# InterfacesA_TRANSCEIVER.net
KiCad netlist of a schematic drawn in Altium Designer
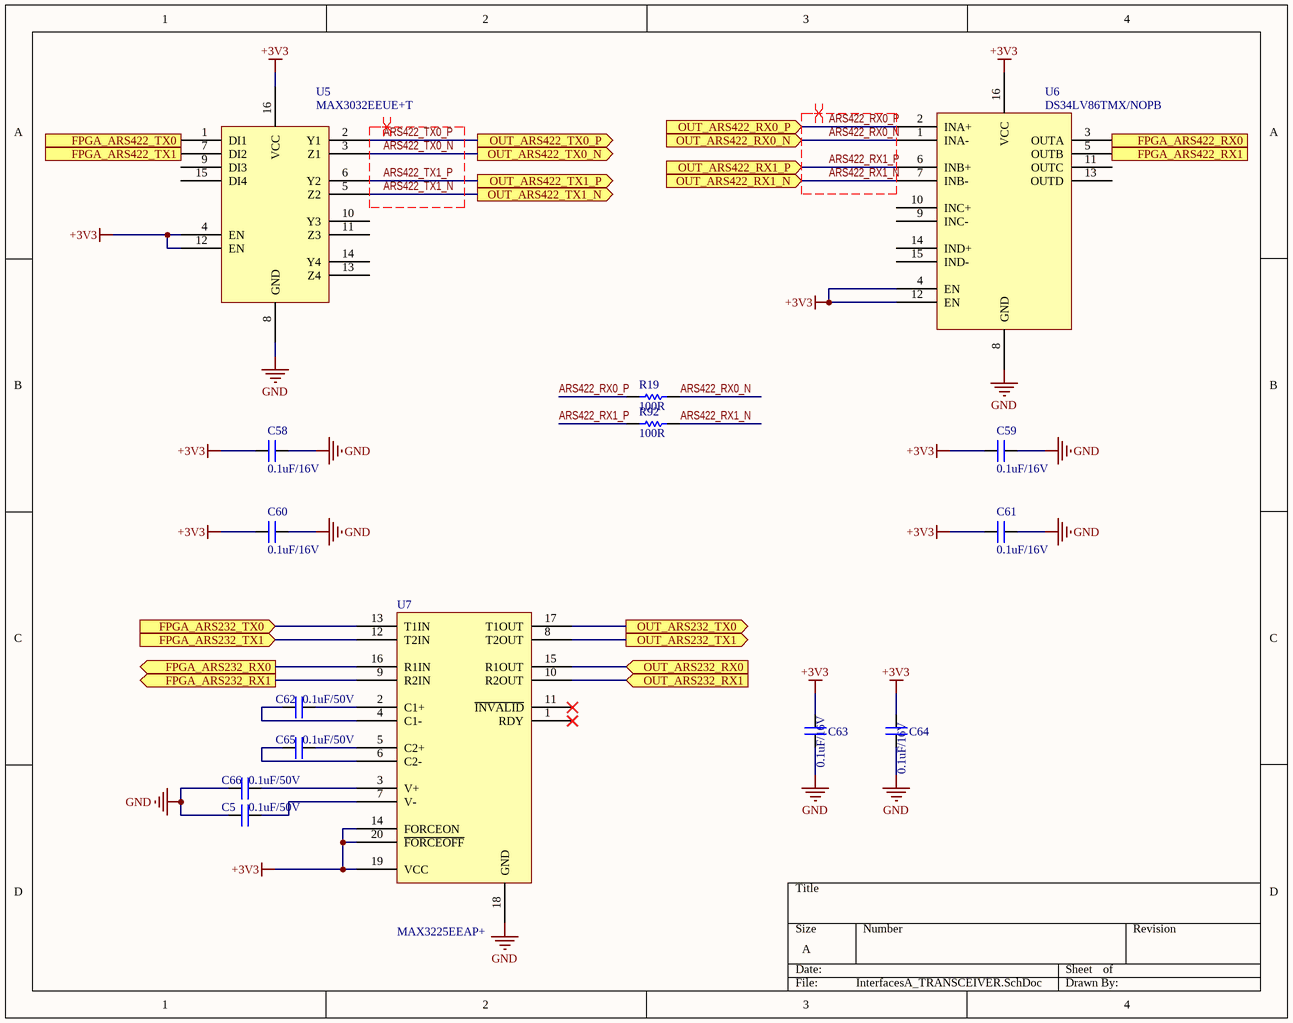
[diagram p0: InterfacesA_TRANSCEIVER.SchDoc]

(export (version "E")
  (design (tool "Eeschema 10.0.6"))
  (components
    (comp (ref "C5")
      (value "0.1uF/50V")
      (footprint "CAP_0805")
      (fields (field (name "Comment") "CAP_0805"))
      (libsource (lib "LibSGQB") (part "CAP_0603"))
    )
    (comp (ref "C58")
      (value "0.1uF/16V")
      (footprint "CAP_0805")
      (fields (field (name "Comment") "CAP_0805"))
      (libsource (lib "LibSGQB") (part "CAP_0603"))
    )
    (comp (ref "C59")
      (value "0.1uF/16V")
      (footprint "CAP_0805")
      (fields (field (name "Comment") "CAP_0805"))
      (libsource (lib "LibSGQB") (part "CAP_0603"))
    )
    (comp (ref "C60")
      (value "0.1uF/16V")
      (footprint "CAP_0805")
      (fields (field (name "Comment") "CAP_0805"))
      (libsource (lib "LibSGQB") (part "CAP_0603"))
    )
    (comp (ref "C61")
      (value "0.1uF/16V")
      (footprint "CAP_0805")
      (fields (field (name "Comment") "CAP_0805"))
      (libsource (lib "LibSGQB") (part "CAP_0603"))
    )
    (comp (ref "C62")
      (value "0.1uF/50V")
      (footprint "CAP_0805")
      (fields (field (name "Comment") "CAP_0805"))
      (libsource (lib "LibSGQB") (part "CAP_0603"))
    )
    (comp (ref "C63")
      (value "0.1uF/16V")
      (footprint "CAP_0805")
      (fields (field (name "Comment") "CAP_0805"))
      (libsource (lib "LibSGQB") (part "CAP_0603"))
    )
    (comp (ref "C64")
      (value "0.1uF/16V")
      (footprint "CAP_0805")
      (fields (field (name "Comment") "CAP_0805"))
      (libsource (lib "LibSGQB") (part "CAP_0603"))
    )
    (comp (ref "C65")
      (value "0.1uF/50V")
      (footprint "CAP_0805")
      (fields (field (name "Comment") "CAP_0805"))
      (libsource (lib "LibSGQB") (part "CAP_0603"))
    )
    (comp (ref "C66")
      (value "0.1uF/50V")
      (footprint "CAP_0805")
      (fields (field (name "Comment") "CAP_0805"))
      (libsource (lib "LibSGQB") (part "CAP_0603"))
    )
    (comp (ref "R19")
      (value "100R")
      (footprint "RES_0805")
      (fields (field (name "Comment") "RES_0805"))
      (libsource (lib "AdapterLib") (part "RES_0805"))
    )
    (comp (ref "R92")
      (value "100R")
      (footprint "RES_0805")
      (fields (field (name "Comment") "RES_0805"))
      (libsource (lib "AdapterLib") (part "RES_0805"))
    )
    (comp (ref "U5")
      (value "MAX3032EEUE+T")
      (footprint "MAX3032EEUE+T")
      (libsource (lib "AdapterLib") (part "MAX3032EEUE+T"))
    )
    (comp (ref "U6")
      (value "DS34LV86TMX/NOPB")
      (footprint "DS34LV86TMX/NOPB")
      (libsource (lib "AdapterLib") (part "DS34LV86TMX/NOPB"))
    )
    (comp (ref "U7")
      (value "MAX3225EEAP+")
      (footprint "MAX3225EEAP+")
      (libsource (lib "AdapterLib") (part "MAX3225EEAP+"))
    )
  )
  (nets
    (net (code "1") (name "+3V3") (class "Default")
      (node (ref "C58") (pin "2") (pinfunction "2_2") (pintype "passive"))
      (node (ref "C59") (pin "2") (pinfunction "2_2") (pintype "passive"))
      (node (ref "C60") (pin "2") (pinfunction "2_2") (pintype "passive"))
      (node (ref "C61") (pin "2") (pinfunction "2_2") (pintype "passive"))
      (node (ref "C63") (pin "2") (pinfunction "2_2") (pintype "passive"))
      (node (ref "C64") (pin "2") (pinfunction "2_2") (pintype "passive"))
      (node (ref "U5") (pin "12") (pinfunction "EN_12") (pintype "passive"))
      (node (ref "U5") (pin "16") (pinfunction "VCC_16") (pintype "passive"))
      (node (ref "U5") (pin "4") (pinfunction "EN_4") (pintype "passive"))
      (node (ref "U6") (pin "12") (pinfunction "EN_12") (pintype "passive"))
      (node (ref "U6") (pin "16") (pinfunction "VCC_16") (pintype "passive"))
      (node (ref "U6") (pin "4") (pinfunction "EN_4") (pintype "passive"))
      (node (ref "U7") (pin "14") (pinfunction "FORCEON_14") (pintype "passive"))
      (node (ref "U7") (pin "19") (pinfunction "VCC_19") (pintype "passive"))
      (node (ref "U7") (pin "20") (pinfunction "~{FORCEOFF}_20") (pintype "passive"))
    )
    (net (code "2") (name "/ARS422_RX0_N") (class "Default")
      (node (ref "R19") (pin "1") (pinfunction "1_1") (pintype "passive"))
      (node (ref "U6") (pin "1") (pinfunction "INA-_1") (pintype "passive"))
    )
    (net (code "3") (name "/ARS422_RX0_P") (class "Default")
      (node (ref "R19") (pin "2") (pinfunction "2_2") (pintype "passive"))
      (node (ref "U6") (pin "2") (pinfunction "INA+_2") (pintype "passive"))
    )
    (net (code "4") (name "/ARS422_RX1_N") (class "Default")
      (node (ref "R92") (pin "1") (pinfunction "1_1") (pintype "passive"))
      (node (ref "U6") (pin "7") (pinfunction "INB-_7") (pintype "passive"))
    )
    (net (code "5") (name "/ARS422_RX1_P") (class "Default")
      (node (ref "R92") (pin "2") (pinfunction "2_2") (pintype "passive"))
      (node (ref "U6") (pin "6") (pinfunction "INB+_6") (pintype "passive"))
    )
    (net (code "6") (name "/ARS422_TX0_N") (class "Default")
      (node (ref "U5") (pin "3") (pinfunction "Z1_3") (pintype "passive"))
    )
    (net (code "7") (name "/ARS422_TX0_P") (class "Default")
      (node (ref "U5") (pin "2") (pinfunction "Y1_2") (pintype "passive"))
    )
    (net (code "8") (name "/ARS422_TX1_N") (class "Default")
      (node (ref "U5") (pin "5") (pinfunction "Z2_5") (pintype "passive"))
    )
    (net (code "9") (name "/ARS422_TX1_P") (class "Default")
      (node (ref "U5") (pin "6") (pinfunction "Y2_6") (pintype "passive"))
    )
    (net (code "10") (name "/FPGA_ARS232_RX0") (class "Default")
      (node (ref "U7") (pin "16") (pinfunction "R1IN_16") (pintype "passive"))
    )
    (net (code "11") (name "/FPGA_ARS232_RX1") (class "Default")
      (node (ref "U7") (pin "9") (pinfunction "R2IN_9") (pintype "passive"))
    )
    (net (code "12") (name "/FPGA_ARS232_TX0") (class "Default")
      (node (ref "U7") (pin "13") (pinfunction "T1IN_13") (pintype "passive"))
    )
    (net (code "13") (name "/FPGA_ARS232_TX1") (class "Default")
      (node (ref "U7") (pin "12") (pinfunction "T2IN_12") (pintype "passive"))
    )
    (net (code "14") (name "/FPGA_ARS422_RX0") (class "Default")
      (node (ref "U6") (pin "3") (pinfunction "OUTA_3") (pintype "passive"))
    )
    (net (code "15") (name "/FPGA_ARS422_RX1") (class "Default")
      (node (ref "U6") (pin "5") (pinfunction "OUTB_5") (pintype "passive"))
    )
    (net (code "16") (name "/FPGA_ARS422_TX0") (class "Default")
      (node (ref "U5") (pin "1") (pinfunction "DI1_1") (pintype "passive"))
    )
    (net (code "17") (name "/FPGA_ARS422_TX1") (class "Default")
      (node (ref "U5") (pin "7") (pinfunction "DI2_7") (pintype "passive"))
    )
    (net (code "18") (name "/OUT_ARS232_RX0") (class "Default")
      (node (ref "U7") (pin "15") (pinfunction "R1OUT_15") (pintype "passive"))
    )
    (net (code "19") (name "/OUT_ARS232_RX1") (class "Default")
      (node (ref "U7") (pin "10") (pinfunction "R2OUT_10") (pintype "passive"))
    )
    (net (code "20") (name "/OUT_ARS232_TX0") (class "Default")
      (node (ref "U7") (pin "17") (pinfunction "T1OUT_17") (pintype "passive"))
    )
    (net (code "21") (name "/OUT_ARS232_TX1") (class "Default")
      (node (ref "U7") (pin "8") (pinfunction "T2OUT_8") (pintype "passive"))
    )
    (net (code "22") (name "GND") (class "Default")
      (node (ref "C5") (pin "2") (pinfunction "2_2") (pintype "passive"))
      (node (ref "C58") (pin "1") (pinfunction "1_1") (pintype "passive"))
      (node (ref "C59") (pin "1") (pinfunction "1_1") (pintype "passive"))
      (node (ref "C60") (pin "1") (pinfunction "1_1") (pintype "passive"))
      (node (ref "C61") (pin "1") (pinfunction "1_1") (pintype "passive"))
      (node (ref "C63") (pin "1") (pinfunction "1_1") (pintype "passive"))
      (node (ref "C64") (pin "1") (pinfunction "1_1") (pintype "passive"))
      (node (ref "C66") (pin "2") (pinfunction "2_2") (pintype "passive"))
      (node (ref "U5") (pin "8") (pinfunction "GND_8") (pintype "passive"))
      (node (ref "U6") (pin "8") (pinfunction "GND_8") (pintype "passive"))
      (node (ref "U7") (pin "18") (pinfunction "GND_18") (pintype "passive"))
    )
    (net (code "23") (name "Net-(U7-C1+)") (class "Default")
      (node (ref "C62") (pin "1") (pinfunction "1_1") (pintype "passive"))
      (node (ref "U7") (pin "2") (pinfunction "C1+_2") (pintype "passive"))
    )
    (net (code "24") (name "Net-(U7-C1-)") (class "Default")
      (node (ref "C62") (pin "2") (pinfunction "2_2") (pintype "passive"))
      (node (ref "U7") (pin "4") (pinfunction "C1-_4") (pintype "passive"))
    )
    (net (code "25") (name "Net-(U7-C2+)") (class "Default")
      (node (ref "C65") (pin "1") (pinfunction "1_1") (pintype "passive"))
      (node (ref "U7") (pin "5") (pinfunction "C2+_5") (pintype "passive"))
    )
    (net (code "26") (name "Net-(U7-C2-)") (class "Default")
      (node (ref "C65") (pin "2") (pinfunction "2_2") (pintype "passive"))
      (node (ref "U7") (pin "6") (pinfunction "C2-_6") (pintype "passive"))
    )
    (net (code "27") (name "Net-(U7-V+)") (class "Default")
      (node (ref "C66") (pin "1") (pinfunction "1_1") (pintype "passive"))
      (node (ref "U7") (pin "3") (pinfunction "V+_3") (pintype "passive"))
    )
    (net (code "28") (name "Net-(U7-V-)") (class "Default")
      (node (ref "C5") (pin "1") (pinfunction "1_1") (pintype "passive"))
      (node (ref "U7") (pin "7") (pinfunction "V-_7") (pintype "passive"))
    )
    (net (code "29") (name "unconnected-(U5-DI3-Pad9)") (class "Default")
      (node (ref "U5") (pin "9") (pinfunction "DI3_9") (pintype "passive"))
    )
    (net (code "30") (name "unconnected-(U5-DI4-Pad15)") (class "Default")
      (node (ref "U5") (pin "15") (pinfunction "DI4_15") (pintype "passive"))
    )
    (net (code "31") (name "unconnected-(U5-Y3-Pad10)") (class "Default")
      (node (ref "U5") (pin "10") (pinfunction "Y3_10") (pintype "passive"))
    )
    (net (code "32") (name "unconnected-(U5-Y4-Pad14)") (class "Default")
      (node (ref "U5") (pin "14") (pinfunction "Y4_14") (pintype "passive"))
    )
    (net (code "33") (name "unconnected-(U5-Z3-Pad11)") (class "Default")
      (node (ref "U5") (pin "11") (pinfunction "Z3_11") (pintype "passive"))
    )
    (net (code "34") (name "unconnected-(U5-Z4-Pad13)") (class "Default")
      (node (ref "U5") (pin "13") (pinfunction "Z4_13") (pintype "passive"))
    )
    (net (code "35") (name "unconnected-(U6-INC+-Pad10)") (class "Default")
      (node (ref "U6") (pin "10") (pinfunction "INC+_10") (pintype "passive"))
    )
    (net (code "36") (name "unconnected-(U6-INC--Pad9)") (class "Default")
      (node (ref "U6") (pin "9") (pinfunction "INC-_9") (pintype "passive"))
    )
    (net (code "37") (name "unconnected-(U6-IND+-Pad14)") (class "Default")
      (node (ref "U6") (pin "14") (pinfunction "IND+_14") (pintype "passive"))
    )
    (net (code "38") (name "unconnected-(U6-IND--Pad15)") (class "Default")
      (node (ref "U6") (pin "15") (pinfunction "IND-_15") (pintype "passive"))
    )
    (net (code "39") (name "unconnected-(U6-OUTC-Pad11)") (class "Default")
      (node (ref "U6") (pin "11") (pinfunction "OUTC_11") (pintype "passive"))
    )
    (net (code "40") (name "unconnected-(U6-OUTD-Pad13)") (class "Default")
      (node (ref "U6") (pin "13") (pinfunction "OUTD_13") (pintype "passive"))
    )
    (net (code "41") (name "unconnected-(U7-RDY-Pad1)") (class "Default")
      (node (ref "U7") (pin "1") (pinfunction "RDY_1") (pintype "passive+no_connect"))
    )
    (net (code "42") (name "unconnected-(U7-~{INVALID}-Pad11)") (class "Default")
      (node (ref "U7") (pin "11") (pinfunction "~{INVALID}_11") (pintype "passive+no_connect"))
    )
  )
)
